# esp_altimeter.net
KiCad netlist of a schematic drawn in Altium Designer
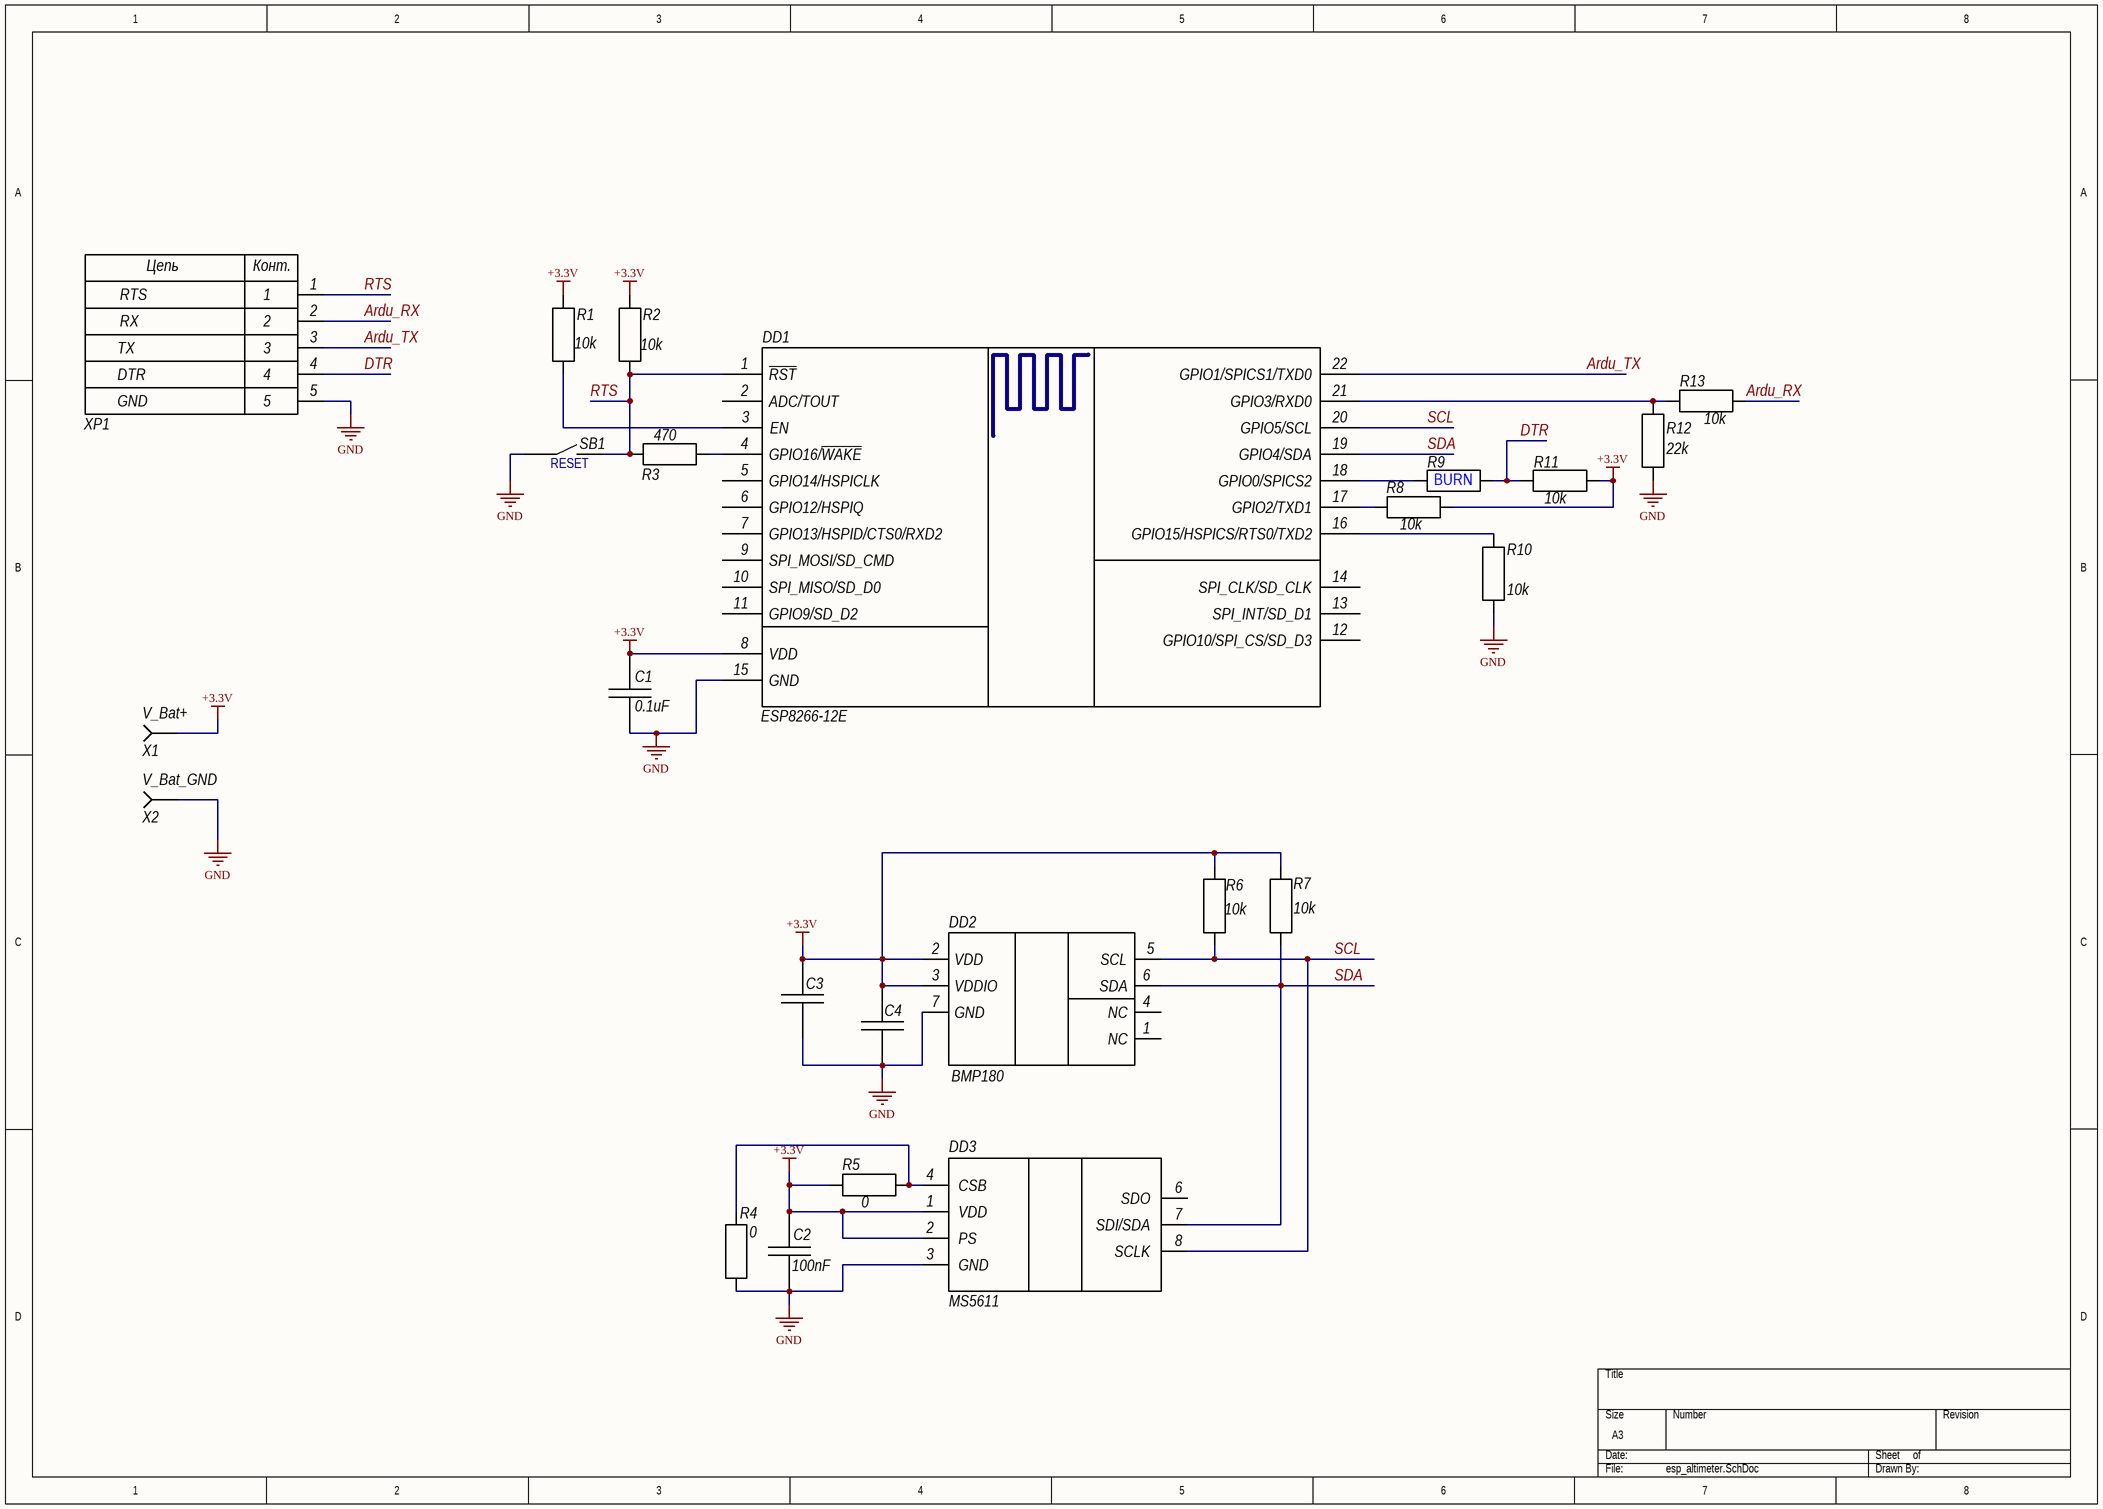
[diagram p0: esp_altimeter.SchDoc]

(export (version "E")
  (design (tool "Eeschema 10.0.6"))
  (components
    (comp (ref "C1")
      (value "0.1uF")
      (footprint "CAP EIA 0603")
      (fields (field (name "Comment") "Cap EIA 0603"))
      (libsource (lib "Capacitors") (part "Cap EIA 0603"))
    )
    (comp (ref "C2")
      (value "100nF")
      (footprint "CAP EIA 0603")
      (fields (field (name "Comment") "Cap EIA 0603"))
      (libsource (lib "Capacitors") (part "Cap EIA 0603"))
    )
    (comp (ref "C3")
      (value "Cap EIA 0603")
      (footprint "CAP EIA 0603")
      (libsource (lib "Capacitors") (part "Cap EIA 0603"))
    )
    (comp (ref "C4")
      (value "Cap EIA 0603")
      (footprint "CAP EIA 0603")
      (libsource (lib "Capacitors") (part "Cap EIA 0603"))
    )
    (comp (ref "DD1")
      (value "ESP8266-12E")
      (footprint "ESP8266 ESP-12-E")
      (libsource (lib "esp8266_library") (part "ESP8266 ESP-12E-RU"))
    )
    (comp (ref "DD2")
      (value "BMP180")
      (footprint "BMP180")
      (fields (field (name "MANUFACTURER") "Bosch") (field (name "NAME") "BMP180"))
      (libsource (lib "Integrated_Circuits") (part "BMP180"))
    )
    (comp (ref "DD3")
      (value "MS5611")
      (footprint "MS5611")
      (libsource (lib "Integrated_Circuits") (part "MS5611"))
    )
    (comp (ref "R1")
      (value "10k")
      (footprint "RES EIA 0603")
      (fields (field (name "Comment") "Res EIA 0603"))
      (libsource (lib "Resistors") (part "Res EIA 0603"))
    )
    (comp (ref "R2")
      (value "10k")
      (footprint "RES EIA 0603")
      (fields (field (name "Comment") "Res EIA 0603"))
      (libsource (lib "Resistors") (part "Res EIA 0603"))
    )
    (comp (ref "R3")
      (value "470")
      (footprint "RES EIA 0603")
      (fields (field (name "Comment") "Res EIA 0603"))
      (libsource (lib "Resistors") (part "Res EIA 0603"))
    )
    (comp (ref "R4")
      (value "0")
      (footprint "RES EIA 0402")
      (fields (field (name "Comment") "Res EIA 0402"))
      (libsource (lib "Resistors") (part "Res EIA 0402"))
    )
    (comp (ref "R5")
      (value "0")
      (footprint "RES EIA 0402")
      (fields (field (name "Comment") "Res EIA 0402"))
      (libsource (lib "Resistors") (part "Res EIA 0402"))
    )
    (comp (ref "R6")
      (value "10k")
      (footprint "RES EIA 0603")
      (fields (field (name "Comment") "Res EIA 0603"))
      (libsource (lib "Resistors") (part "Res EIA 0603"))
    )
    (comp (ref "R7")
      (value "10k")
      (footprint "RES EIA 0603")
      (fields (field (name "Comment") "Res EIA 0603"))
      (libsource (lib "Resistors") (part "Res EIA 0603"))
    )
    (comp (ref "R8")
      (value "10k")
      (footprint "RES EIA 0603")
      (fields (field (name "Comment") "Res EIA 0603"))
      (libsource (lib "Resistors") (part "Res EIA 0603"))
    )
    (comp (ref "R9")
      (value "BURN")
      (footprint "RES EIA 0603")
      (libsource (lib "Resistors") (part "Res EIA 0603"))
    )
    (comp (ref "R10")
      (value "10k")
      (footprint "RES EIA 0603")
      (fields (field (name "Comment") "Res EIA 0603"))
      (libsource (lib "Resistors") (part "Res EIA 0603"))
    )
    (comp (ref "R11")
      (value "10k")
      (footprint "RES EIA 0603")
      (fields (field (name "Comment") "Res EIA 0603"))
      (libsource (lib "Resistors") (part "Res EIA 0603"))
    )
    (comp (ref "R12")
      (value "22k")
      (footprint "RES EIA 0603")
      (fields (field (name "Comment") "Res EIA 0603"))
      (libsource (lib "Resistors") (part "Res EIA 0603"))
    )
    (comp (ref "R13")
      (value "10k")
      (footprint "RES EIA 0603")
      (fields (field (name "Comment") "Res EIA 0603"))
      (libsource (lib "Resistors") (part "Res EIA 0603"))
    )
    (comp (ref "SB1")
      (value "RESET")
      (footprint "SB_Connector")
      (fields (field (name "MANUFACTURER") "A_Gorbunov"))
      (libsource (lib "Connectors") (part "SB_STM_Type"))
    )
    (comp (ref "X1")
      (value "V_Bat+")
      (footprint "Pin - Referal")
      (description "Generic Pin Contact")
      (libsource (lib "Connectors") (part "Pin_Referal"))
    )
    (comp (ref "X2")
      (value "V_Bat_GND")
      (footprint "Pin - Referal")
      (description "Generic Pin Contact")
      (libsource (lib "Connectors") (part "Pin_Referal"))
    )
    (comp (ref "XP1")
      (value "BM05B-SRSS-TB")
      (footprint "BM05B-SRSS-TB")
      (description "5-Pin Angle Connector")
      (fields (field (name "MANUFACTURER") "JST"))
      (libsource (lib "Connectors") (part "BM05B-SRSS-TB"))
    )
  )
  (nets
    (net (code "1") (name "+3.3V") (class "Default")
      (node (ref "C1") (pin "2") (pinfunction "2_2") (pintype "passive"))
      (node (ref "C2") (pin "2") (pinfunction "2_2") (pintype "passive"))
      (node (ref "C3") (pin "2") (pinfunction "2_2") (pintype "passive"))
      (node (ref "C4") (pin "2") (pinfunction "2_2") (pintype "passive"))
      (node (ref "DD1") (pin "8") (pinfunction "VDD_8") (pintype "passive"))
      (node (ref "DD2") (pin "2") (pinfunction "VDD_2") (pintype "passive"))
      (node (ref "DD2") (pin "3") (pinfunction "VDDIO_3") (pintype "passive"))
      (node (ref "DD3") (pin "1") (pinfunction "VDD_1") (pintype "passive"))
      (node (ref "DD3") (pin "2") (pinfunction "PS_2") (pintype "passive"))
      (node (ref "R1") (pin "2") (pinfunction "2_2") (pintype "passive"))
      (node (ref "R11") (pin "2") (pinfunction "2_2") (pintype "passive"))
      (node (ref "R2") (pin "2") (pinfunction "2_2") (pintype "passive"))
      (node (ref "R5") (pin "2") (pinfunction "2_2") (pintype "passive"))
      (node (ref "R6") (pin "2") (pinfunction "2_2") (pintype "passive"))
      (node (ref "R7") (pin "2") (pinfunction "2_2") (pintype "passive"))
      (node (ref "R8") (pin "2") (pinfunction "2_2") (pintype "passive"))
      (node (ref "X1") (pin "1") (pinfunction "1_1") (pintype "passive"))
    )
    (net (code "2") (name "/Ardu_RX") (class "Default")
      (node (ref "R13") (pin "2") (pinfunction "2_2") (pintype "passive"))
      (node (ref "XP1") (pin "2") (pinfunction "2_2") (pintype "passive"))
    )
    (net (code "3") (name "/Ardu_TX") (class "Default")
      (node (ref "DD1") (pin "22") (pinfunction "GPIO1/SPICS1/TXD0_22") (pintype "passive"))
      (node (ref "XP1") (pin "3") (pinfunction "3_3") (pintype "passive"))
    )
    (net (code "4") (name "/DTR") (class "Default")
      (node (ref "R11") (pin "1") (pinfunction "1_1") (pintype "passive"))
      (node (ref "R9") (pin "2") (pinfunction "2_2") (pintype "passive"))
      (node (ref "XP1") (pin "4") (pinfunction "4_4") (pintype "passive"))
    )
    (net (code "5") (name "/RTS") (class "Default")
      (node (ref "DD1") (pin "1") (pinfunction "~{RST}_1") (pintype "passive"))
      (node (ref "R2") (pin "1") (pinfunction "1_1") (pintype "passive"))
      (node (ref "R3") (pin "1") (pinfunction "1_1") (pintype "passive"))
      (node (ref "SB1") (pin "2") (pinfunction "2_2") (pintype "passive"))
      (node (ref "XP1") (pin "1") (pinfunction "1_1") (pintype "passive"))
    )
    (net (code "6") (name "/SCL") (class "Default")
      (node (ref "DD1") (pin "20") (pinfunction "GPIO5/SCL_20") (pintype "passive"))
      (node (ref "DD2") (pin "5") (pinfunction "SCL_5") (pintype "passive"))
      (node (ref "DD3") (pin "8") (pinfunction "SCLK_8") (pintype "passive"))
      (node (ref "R6") (pin "1") (pinfunction "1_1") (pintype "passive"))
    )
    (net (code "7") (name "/SDA") (class "Default")
      (node (ref "DD1") (pin "19") (pinfunction "GPIO4/SDA_19") (pintype "passive"))
      (node (ref "DD2") (pin "6") (pinfunction "SDA_6") (pintype "passive"))
      (node (ref "DD3") (pin "7") (pinfunction "SDI/SDA_7") (pintype "passive"))
      (node (ref "R7") (pin "1") (pinfunction "1_1") (pintype "passive"))
    )
    (net (code "8") (name "GND") (class "Default")
      (node (ref "C1") (pin "1") (pinfunction "1_1") (pintype "passive"))
      (node (ref "C2") (pin "1") (pinfunction "1_1") (pintype "passive"))
      (node (ref "C3") (pin "1") (pinfunction "1_1") (pintype "passive"))
      (node (ref "C4") (pin "1") (pinfunction "1_1") (pintype "passive"))
      (node (ref "DD1") (pin "15") (pinfunction "GND_15") (pintype "passive"))
      (node (ref "DD2") (pin "7") (pinfunction "GND_7") (pintype "passive"))
      (node (ref "DD3") (pin "3") (pinfunction "GND_3") (pintype "passive"))
      (node (ref "R10") (pin "1") (pinfunction "1_1") (pintype "passive"))
      (node (ref "R12") (pin "1") (pinfunction "1_1") (pintype "passive"))
      (node (ref "R4") (pin "1") (pinfunction "1_1") (pintype "passive"))
      (node (ref "SB1") (pin "1") (pinfunction "1_1") (pintype "passive"))
      (node (ref "X2") (pin "1") (pinfunction "1_1") (pintype "passive"))
      (node (ref "XP1") (pin "5") (pinfunction "5_5") (pintype "passive"))
    )
    (net (code "9") (name "Net-(DD1-EN)") (class "Default")
      (node (ref "DD1") (pin "3") (pinfunction "EN_3") (pintype "passive"))
      (node (ref "R1") (pin "1") (pinfunction "1_1") (pintype "passive"))
    )
    (net (code "10") (name "Net-(DD1-GPIO0{slash}SPICS2)") (class "Default")
      (node (ref "DD1") (pin "18") (pinfunction "GPIO0/SPICS2_18") (pintype "passive"))
      (node (ref "R9") (pin "1") (pinfunction "1_1") (pintype "passive"))
    )
    (net (code "11") (name "Net-(DD1-GPIO2{slash}TXD1)") (class "Default")
      (node (ref "DD1") (pin "17") (pinfunction "GPIO2/TXD1_17") (pintype "passive"))
      (node (ref "R8") (pin "1") (pinfunction "1_1") (pintype "passive"))
    )
    (net (code "12") (name "Net-(DD1-GPIO3{slash}RXD0)") (class "Default")
      (node (ref "DD1") (pin "21") (pinfunction "GPIO3/RXD0_21") (pintype "passive"))
      (node (ref "R12") (pin "2") (pinfunction "2_2") (pintype "passive"))
      (node (ref "R13") (pin "1") (pinfunction "1_1") (pintype "passive"))
    )
    (net (code "13") (name "Net-(DD1-GPIO15{slash}HSPICS{slash}RTS0{slash}TXD2)") (class "Default")
      (node (ref "DD1") (pin "16") (pinfunction "GPIO15/HSPICS/RTS0/TXD2_16") (pintype "passive"))
      (node (ref "R10") (pin "2") (pinfunction "2_2") (pintype "passive"))
    )
    (net (code "14") (name "Net-(DD1-GPIO16{slash}~{WAKE})") (class "Default")
      (node (ref "DD1") (pin "4") (pinfunction "GPIO16/~{WAKE}_4") (pintype "passive"))
      (node (ref "R3") (pin "2") (pinfunction "2_2") (pintype "passive"))
    )
    (net (code "15") (name "Net-(DD3-CSB-Pad4)") (class "Default")
      (node (ref "DD3") (pin "4") (pinfunction "CSB_4") (pintype "passive"))
      (node (ref "R4") (pin "2") (pinfunction "2_2") (pintype "passive"))
      (node (ref "R5") (pin "1") (pinfunction "1_1") (pintype "passive"))
    )
    (net (code "16") (name "unconnected-(DD1-ADC{slash}TOUT-Pad2)") (class "Default")
      (node (ref "DD1") (pin "2") (pinfunction "ADC/TOUT_2") (pintype "passive"))
    )
    (net (code "17") (name "unconnected-(DD1-GPIO9{slash}SD_D2-Pad11)") (class "Default")
      (node (ref "DD1") (pin "11") (pinfunction "GPIO9/SD_D2_11") (pintype "passive"))
    )
    (net (code "18") (name "unconnected-(DD1-GPIO10{slash}SPI_CS{slash}SD_D3-Pad12)") (class "Default")
      (node (ref "DD1") (pin "12") (pinfunction "GPIO10/SPI_CS/SD_D3_12") (pintype "passive"))
    )
    (net (code "19") (name "unconnected-(DD1-GPIO12{slash}HSPIQ-Pad6)") (class "Default")
      (node (ref "DD1") (pin "6") (pinfunction "GPIO12/HSPIQ_6") (pintype "passive"))
    )
    (net (code "20") (name "unconnected-(DD1-GPIO13{slash}HSPID{slash}CTS0{slash}RXD2-Pad7)") (class "Default")
      (node (ref "DD1") (pin "7") (pinfunction "GPIO13/HSPID/CTS0/RXD2_7") (pintype "passive"))
    )
    (net (code "21") (name "unconnected-(DD1-GPIO14{slash}HSPICLK-Pad5)") (class "Default")
      (node (ref "DD1") (pin "5") (pinfunction "GPIO14/HSPICLK_5") (pintype "passive"))
    )
    (net (code "22") (name "unconnected-(DD1-SPI_CLK{slash}SD_CLK-Pad14)") (class "Default")
      (node (ref "DD1") (pin "14") (pinfunction "SPI_CLK/SD_CLK_14") (pintype "passive"))
    )
    (net (code "23") (name "unconnected-(DD1-SPI_INT{slash}SD_D1-Pad13)") (class "Default")
      (node (ref "DD1") (pin "13") (pinfunction "SPI_INT/SD_D1_13") (pintype "passive"))
    )
    (net (code "24") (name "unconnected-(DD1-SPI_MISO{slash}SD_D0-Pad10)") (class "Default")
      (node (ref "DD1") (pin "10") (pinfunction "SPI_MISO/SD_D0_10") (pintype "passive"))
    )
    (net (code "25") (name "unconnected-(DD1-SPI_MOSI{slash}SD_CMD-Pad9)") (class "Default")
      (node (ref "DD1") (pin "9") (pinfunction "SPI_MOSI/SD_CMD_9") (pintype "passive"))
    )
    (net (code "26") (name "unconnected-(DD2-NC-Pad1)") (class "Default")
      (node (ref "DD2") (pin "1") (pinfunction "NC_1") (pintype "passive"))
    )
    (net (code "27") (name "unconnected-(DD2-NC-Pad4)") (class "Default")
      (node (ref "DD2") (pin "4") (pinfunction "NC_4") (pintype "passive"))
    )
    (net (code "28") (name "unconnected-(DD3-CSB-Pad5)") (class "Default")
      (node (ref "DD3") (pin "5") (pinfunction "CSB_5") (pintype "passive"))
    )
    (net (code "29") (name "unconnected-(DD3-SDO-Pad6)") (class "Default")
      (node (ref "DD3") (pin "6") (pinfunction "SDO_6") (pintype "passive"))
    )
  )
)
